# Desain_hardware_GasMeter.net
KiCad netlist of a schematic drawn in EAGLE
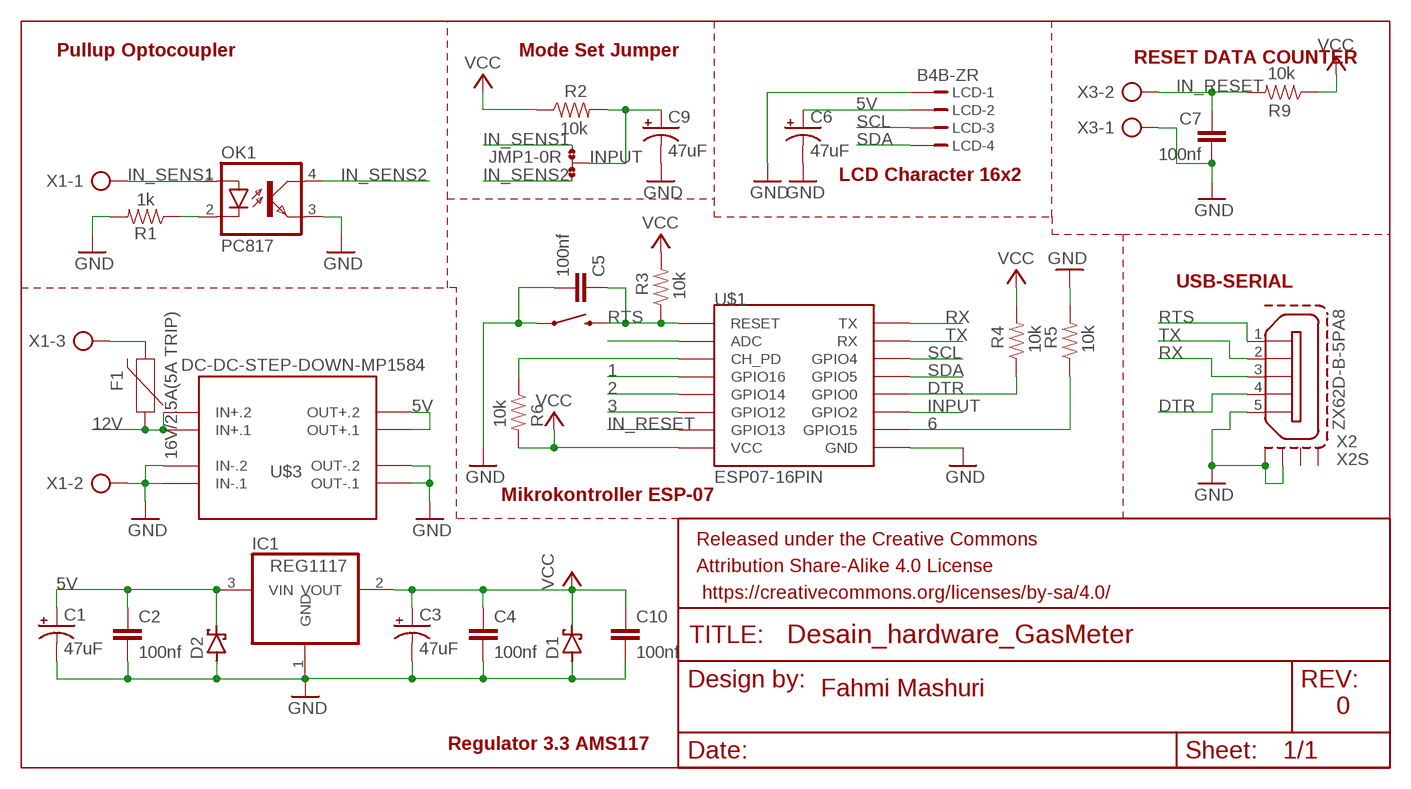
[diagram p0: schematic, sheet 1]

(export (version "E")
  (design (tool "Eeschema 10.0.6"))
  (components
    (comp (ref "C1")
      (value "47uF")
      (footprint "eagle-import:EIA3528")
      (libsource (lib "eagle-import") (part "47UF-POLAR-EIA3528-10V-10%"))
    )
    (comp (ref "C2")
      (value "100nf")
      (footprint "eagle-import:0805")
      (libsource (lib "eagle-import") (part "39NF-0805-50V-10%"))
    )
    (comp (ref "C3")
      (value "47uF")
      (footprint "eagle-import:EIA3528")
      (libsource (lib "eagle-import") (part "47UF-POLAR-EIA3528-10V-10%"))
    )
    (comp (ref "C4")
      (value "100nf")
      (footprint "eagle-import:0805")
      (libsource (lib "eagle-import") (part "39NF-0805-50V-10%"))
    )
    (comp (ref "C5")
      (value "100nf")
      (footprint "eagle-import:0805")
      (libsource (lib "eagle-import") (part "39NF-0805-50V-10%"))
    )
    (comp (ref "C6")
      (value "47uF")
      (footprint "eagle-import:EIA3528")
      (libsource (lib "eagle-import") (part "47UF-POLAR-EIA3528-10V-10%"))
    )
    (comp (ref "C7")
      (value "100nf")
      (footprint "eagle-import:0805")
      (libsource (lib "eagle-import") (part "39NF-0805-50V-10%"))
    )
    (comp (ref "C9")
      (value "47uF")
      (footprint "eagle-import:EIA3528")
      (libsource (lib "eagle-import") (part "47UF-POLAR-EIA3528-10V-10%"))
    )
    (comp (ref "C10")
      (value "100nf")
      (footprint "eagle-import:0805")
      (libsource (lib "eagle-import") (part "39NF-0805-50V-10%"))
    )
    (comp (ref "D1")
      (value "SCHOTTKY-DIODESMD")
      (footprint "eagle-import:SMB")
      (libsource (lib "eagle-import") (part "SCHOTTKY-DIODESMD"))
    )
    (comp (ref "D2")
      (value "SCHOTTKY-DIODESMD")
      (footprint "eagle-import:SMB")
      (libsource (lib "eagle-import") (part "SCHOTTKY-DIODESMD"))
    )
    (comp (ref "F1")
      (value "16V/2.5A(5A TRIP)")
      (footprint "eagle-import:1812")
      (libsource (lib "eagle-import") (part "PPTC_16V_2.5A"))
    )
    (comp (ref "FRAME1")
      (value "FRAME-LETTER")
      (footprint "eagle-import:CREATIVE_COMMONS")
      (libsource (lib "eagle-import") (part "FRAME-LETTER"))
    )
    (comp (ref "IC1")
      (value "REG1117")
      (footprint "eagle-import:SOT223")
      (libsource (lib "eagle-import") (part "REG1117"))
    )
    (comp (ref "JMP1")
      (value "0R-JUMPA")
      (footprint "eagle-import:A0R-JMP")
      (libsource (lib "eagle-import") (part "0R-JUMPA"))
    )
    (comp (ref "LCD")
      (value "B4B-ZR")
      (footprint "eagle-import:B4B-ZR")
      (fields (field (name "MF") "FARNELL") (field (name "MPN") "B4B-ZR(LF)(SN)"))
      (libsource (lib "eagle-import") (part "?4B-ZRB"))
    )
    (comp (ref "OK1")
      (value "PC817")
      (footprint "eagle-import:DIL04")
      (fields (field (name "MPN") "PC817X4J000F"))
      (libsource (lib "eagle-import") (part "PC817"))
    )
    (comp (ref "R1")
      (value "1k")
      (footprint "eagle-import:1210")
      (libsource (lib "eagle-import") (part "0.1OHM-1210-1/2W-1%"))
    )
    (comp (ref "R2")
      (value "10k")
      (footprint "eagle-import:0805")
      (libsource (lib "eagle-import") (part "0.3OHM-0805-1/8W-1%"))
    )
    (comp (ref "R3")
      (value "10k")
      (footprint "eagle-import:0805")
      (libsource (lib "eagle-import") (part "0.3OHM-0805-1/8W-1%"))
    )
    (comp (ref "R4")
      (value "10k")
      (footprint "eagle-import:0805")
      (libsource (lib "eagle-import") (part "0.3OHM-0805-1/8W-1%"))
    )
    (comp (ref "R5")
      (value "10k")
      (footprint "eagle-import:0805")
      (libsource (lib "eagle-import") (part "0.3OHM-0805-1/8W-1%"))
    )
    (comp (ref "R6")
      (value "10k")
      (footprint "eagle-import:0805")
      (libsource (lib "eagle-import") (part "0.3OHM-0805-1/8W-1%"))
    )
    (comp (ref "R9")
      (value "10k")
      (footprint "eagle-import:0805")
      (libsource (lib "eagle-import") (part "0.3OHM-0805-1/8W-1%"))
    )
    (comp (ref "U$1")
      (value "ESP07-16PIN")
      (footprint "eagle-import:ESP07-16PIN")
      (libsource (lib "eagle-import") (part "ESP07-16PIN"))
    )
    (comp (ref "U$2")
      (value "MOMENTARY-SWITCH-SPST-PTH-6.0MM")
      (footprint "eagle-import:TACTILE_SWITCH_PTH_6.0MM")
      (libsource (lib "eagle-import") (part "MOMENTARY-SWITCH-SPST-PTH-6.0MM"))
    )
    (comp (ref "U$3")
      (value "DC-DC-STEP-DOWN-MP1584")
      (footprint "eagle-import:DC-DC-STEP-DOWN-MP1584")
      (libsource (lib "eagle-import") (part "DC-DC-STEP-DOWN-MP1584"))
    )
    (comp (ref "X1")
      (value "AK500/3")
      (footprint "eagle-import:AK500_3")
      (libsource (lib "eagle-import") (part "AK500/3"))
    )
    (comp (ref "X2")
      (value "ZX62D-B-5PA8")
      (footprint "eagle-import:ZX62D-B-5PA8")
      (fields (field (name "MF") "Hirose"))
      (libsource (lib "eagle-import") (part "ZX62D-B-5PA8"))
    )
    (comp (ref "X3")
      (value "AK500/2")
      (footprint "eagle-import:AK500_2")
      (libsource (lib "eagle-import") (part "AK500/2"))
    )
  )
  (nets
    (net (code "1") (name "/1") (class "Default")
      (node (ref "U$1") (pin "GPIO16") (pinfunction "GPIO16_GPIO16") (pintype "bidirectional"))
    )
    (net (code "2") (name "/2") (class "Default")
      (node (ref "U$1") (pin "GPIO14") (pinfunction "GPIO14_GPIO14") (pintype "bidirectional"))
    )
    (net (code "3") (name "/3") (class "Default")
      (node (ref "U$1") (pin "GPIO12") (pinfunction "GPIO12_GPIO12") (pintype "bidirectional"))
    )
    (net (code "4") (name "/5V") (class "Default")
      (node (ref "C1") (pin "A") (pinfunction "+_A") (pintype "passive"))
      (node (ref "C2") (pin "1") (pinfunction "1_1") (pintype "passive"))
      (node (ref "C6") (pin "A") (pinfunction "+_A") (pintype "passive"))
      (node (ref "D2") (pin "C") (pinfunction "C_C") (pintype "passive"))
      (node (ref "IC1") (pin "3") (pinfunction "VIN_3") (pintype "input"))
      (node (ref "LCD") (pin "2") (pinfunction "1_2") (pintype "passive"))
      (node (ref "U$3") (pin "OUT+.1") (pinfunction "OUT+.1_OUT+.1") (pintype "bidirectional"))
      (node (ref "U$3") (pin "OUT+.2") (pinfunction "OUT+.2_OUT+.2") (pintype "bidirectional"))
    )
    (net (code "5") (name "/6") (class "Default")
      (node (ref "R5") (pin "1") (pinfunction "1_1") (pintype "passive"))
      (node (ref "U$1") (pin "GPIO15") (pinfunction "GPIO15_GPIO15") (pintype "bidirectional"))
    )
    (net (code "6") (name "/12V") (class "Default")
      (node (ref "F1") (pin "1") (pinfunction "1_1") (pintype "bidirectional"))
      (node (ref "U$3") (pin "IN+.1") (pinfunction "IN+.1_IN+.1") (pintype "bidirectional"))
      (node (ref "U$3") (pin "IN+.2") (pinfunction "IN+.2_IN+.2") (pintype "bidirectional"))
    )
    (net (code "7") (name "/DTR") (class "Default")
      (node (ref "R4") (pin "1") (pinfunction "1_1") (pintype "passive"))
      (node (ref "U$1") (pin "GPIO0") (pinfunction "GPIO0_GPIO0") (pintype "bidirectional"))
      (node (ref "X2") (pin "4") (pinfunction "4_4") (pintype "passive"))
    )
    (net (code "8") (name "/INPUT") (class "Default")
      (node (ref "C9") (pin "A") (pinfunction "+_A") (pintype "passive"))
      (node (ref "JMP1") (pin "2") (pinfunction "2_2") (pintype "passive"))
      (node (ref "R2") (pin "2") (pinfunction "2_2") (pintype "passive"))
      (node (ref "U$1") (pin "GPIO2") (pinfunction "GPIO2_GPIO2") (pintype "bidirectional"))
    )
    (net (code "9") (name "/IN_RESET") (class "Default")
      (node (ref "C7") (pin "1") (pinfunction "1_1") (pintype "passive"))
      (node (ref "R9") (pin "2") (pinfunction "2_2") (pintype "passive"))
      (node (ref "U$1") (pin "GPIO13") (pinfunction "GPIO13_GPIO13") (pintype "bidirectional"))
      (node (ref "X3") (pin "2") (pinfunction "KL_2") (pintype "passive"))
    )
    (net (code "10") (name "/IN_SENS1") (class "Default")
      (node (ref "JMP1") (pin "1") (pinfunction "1_1") (pintype "passive"))
      (node (ref "OK1") (pin "1") (pinfunction "A_1") (pintype "passive"))
      (node (ref "X1") (pin "1") (pinfunction "KL_1") (pintype "passive"))
    )
    (net (code "11") (name "/IN_SENS2") (class "Default")
      (node (ref "JMP1") (pin "3") (pinfunction "3_3") (pintype "passive"))
      (node (ref "OK1") (pin "4") (pinfunction "COL_4") (pintype "passive"))
    )
    (net (code "12") (name "/RTS") (class "Default")
      (node (ref "C5") (pin "1") (pinfunction "1_1") (pintype "passive"))
      (node (ref "R3") (pin "1") (pinfunction "1_1") (pintype "passive"))
      (node (ref "U$1") (pin "REST") (pinfunction "RESET_REST") (pintype "bidirectional"))
      (node (ref "U$2") (pin "3") (pinfunction "2_3") (pintype "passive"))
      (node (ref "X2") (pin "1") (pinfunction "1_1") (pintype "passive"))
    )
    (net (code "13") (name "/RX") (class "Default")
      (node (ref "U$1") (pin "TX") (pinfunction "TX_TX") (pintype "bidirectional"))
      (node (ref "X2") (pin "3") (pinfunction "3_3") (pintype "passive"))
    )
    (net (code "14") (name "/SCL") (class "Default")
      (node (ref "LCD") (pin "3") (pinfunction "1_3") (pintype "passive"))
      (node (ref "U$1") (pin "GPIO4") (pinfunction "GPIO4_GPIO4") (pintype "bidirectional"))
    )
    (net (code "15") (name "/SDA") (class "Default")
      (node (ref "LCD") (pin "4") (pinfunction "1_4") (pintype "passive"))
      (node (ref "U$1") (pin "GPIO5") (pinfunction "GPIO5_GPIO5") (pintype "bidirectional"))
    )
    (net (code "16") (name "/TX") (class "Default")
      (node (ref "U$1") (pin "RX") (pinfunction "RX_RX") (pintype "bidirectional"))
      (node (ref "X2") (pin "2") (pinfunction "2_2") (pintype "passive"))
    )
    (net (code "17") (name "GND") (class "Default")
      (node (ref "C1") (pin "C") (pinfunction "-_C") (pintype "passive"))
      (node (ref "C10") (pin "2") (pinfunction "2_2") (pintype "passive"))
      (node (ref "C2") (pin "2") (pinfunction "2_2") (pintype "passive"))
      (node (ref "C3") (pin "C") (pinfunction "-_C") (pintype "passive"))
      (node (ref "C4") (pin "2") (pinfunction "2_2") (pintype "passive"))
      (node (ref "C5") (pin "2") (pinfunction "2_2") (pintype "passive"))
      (node (ref "C6") (pin "C") (pinfunction "-_C") (pintype "passive"))
      (node (ref "C7") (pin "2") (pinfunction "2_2") (pintype "passive"))
      (node (ref "C9") (pin "C") (pinfunction "-_C") (pintype "passive"))
      (node (ref "D1") (pin "A") (pinfunction "A_A") (pintype "passive"))
      (node (ref "D2") (pin "A") (pinfunction "A_A") (pintype "passive"))
      (node (ref "IC1") (pin "1") (pinfunction "GND_1") (pintype "power_in"))
      (node (ref "LCD") (pin "1") (pinfunction "1_1") (pintype "passive"))
      (node (ref "OK1") (pin "3") (pinfunction "EMIT_3") (pintype "passive"))
      (node (ref "R1") (pin "2") (pinfunction "2_2") (pintype "passive"))
      (node (ref "R5") (pin "2") (pinfunction "2_2") (pintype "passive"))
      (node (ref "U$1") (pin "GND") (pinfunction "GND_GND") (pintype "bidirectional"))
      (node (ref "U$2") (pin "1") (pinfunction "1_1") (pintype "passive"))
      (node (ref "U$3") (pin "IN-.1") (pinfunction "IN-.1_IN-.1") (pintype "bidirectional"))
      (node (ref "U$3") (pin "IN-.2") (pinfunction "IN-.2_IN-.2") (pintype "bidirectional"))
      (node (ref "U$3") (pin "OUT-.1") (pinfunction "OUT-.1_OUT-.1") (pintype "bidirectional"))
      (node (ref "U$3") (pin "OUT-.2") (pinfunction "OUT-.2_OUT-.2") (pintype "bidirectional"))
      (node (ref "X1") (pin "2") (pinfunction "KL_2") (pintype "passive"))
      (node (ref "X2") (pin "5") (pinfunction "5_5") (pintype "passive"))
      (node (ref "X2") (pin "S1") (pinfunction "S1_S1") (pintype "passive"))
      (node (ref "X2") (pin "S2") (pinfunction "S2_S2") (pintype "passive"))
      (node (ref "X3") (pin "1") (pinfunction "KL_1") (pintype "passive"))
    )
    (net (code "18") (name "Net-(OK1-C)") (class "Default")
      (node (ref "OK1") (pin "2") (pinfunction "C_2") (pintype "passive"))
      (node (ref "R1") (pin "1") (pinfunction "1_1") (pintype "passive"))
    )
    (net (code "19") (name "Net-(R6-Pad1)") (class "Default")
      (node (ref "R6") (pin "1") (pinfunction "1_1") (pintype "passive"))
      (node (ref "U$1") (pin "CH_PD") (pinfunction "CH_PD_CH_PD") (pintype "bidirectional"))
    )
    (net (code "20") (name "Net-(X1C-KL)") (class "Default")
      (node (ref "F1") (pin "2") (pinfunction "2_2") (pintype "bidirectional"))
      (node (ref "X1") (pin "3") (pinfunction "KL_3") (pintype "passive"))
    )
    (net (code "21") (name "VCC") (class "Default")
      (node (ref "C10") (pin "1") (pinfunction "1_1") (pintype "passive"))
      (node (ref "C3") (pin "A") (pinfunction "+_A") (pintype "passive"))
      (node (ref "C4") (pin "1") (pinfunction "1_1") (pintype "passive"))
      (node (ref "D1") (pin "C") (pinfunction "C_C") (pintype "passive"))
      (node (ref "IC1") (pin "2") (pinfunction "VOUT_2") (pintype "output"))
      (node (ref "R2") (pin "1") (pinfunction "1_1") (pintype "passive"))
      (node (ref "R3") (pin "2") (pinfunction "2_2") (pintype "passive"))
      (node (ref "R4") (pin "2") (pinfunction "2_2") (pintype "passive"))
      (node (ref "R6") (pin "2") (pinfunction "2_2") (pintype "passive"))
      (node (ref "R9") (pin "1") (pinfunction "1_1") (pintype "passive"))
      (node (ref "U$1") (pin "VCC") (pinfunction "VCC_VCC") (pintype "bidirectional"))
    )
    (net (code "22") (name "unconnected-(U$1-PadADC)") (class "Default")
      (node (ref "U$1") (pin "ADC") (pinfunction "ADC_ADC") (pintype "bidirectional"))
    )
    (net (code "23") (name "unconnected-(X2-PadS3)") (class "Default")
      (node (ref "X2") (pin "S3") (pinfunction "S3_S3") (pintype "passive"))
    )
    (net (code "24") (name "unconnected-(X2-PadS4)") (class "Default")
      (node (ref "X2") (pin "S4") (pinfunction "S4_S4") (pintype "passive"))
    )
  )
)
